# Nervo_Board_InMoov.net
KiCad netlist of a schematic drawn in EasyEDA
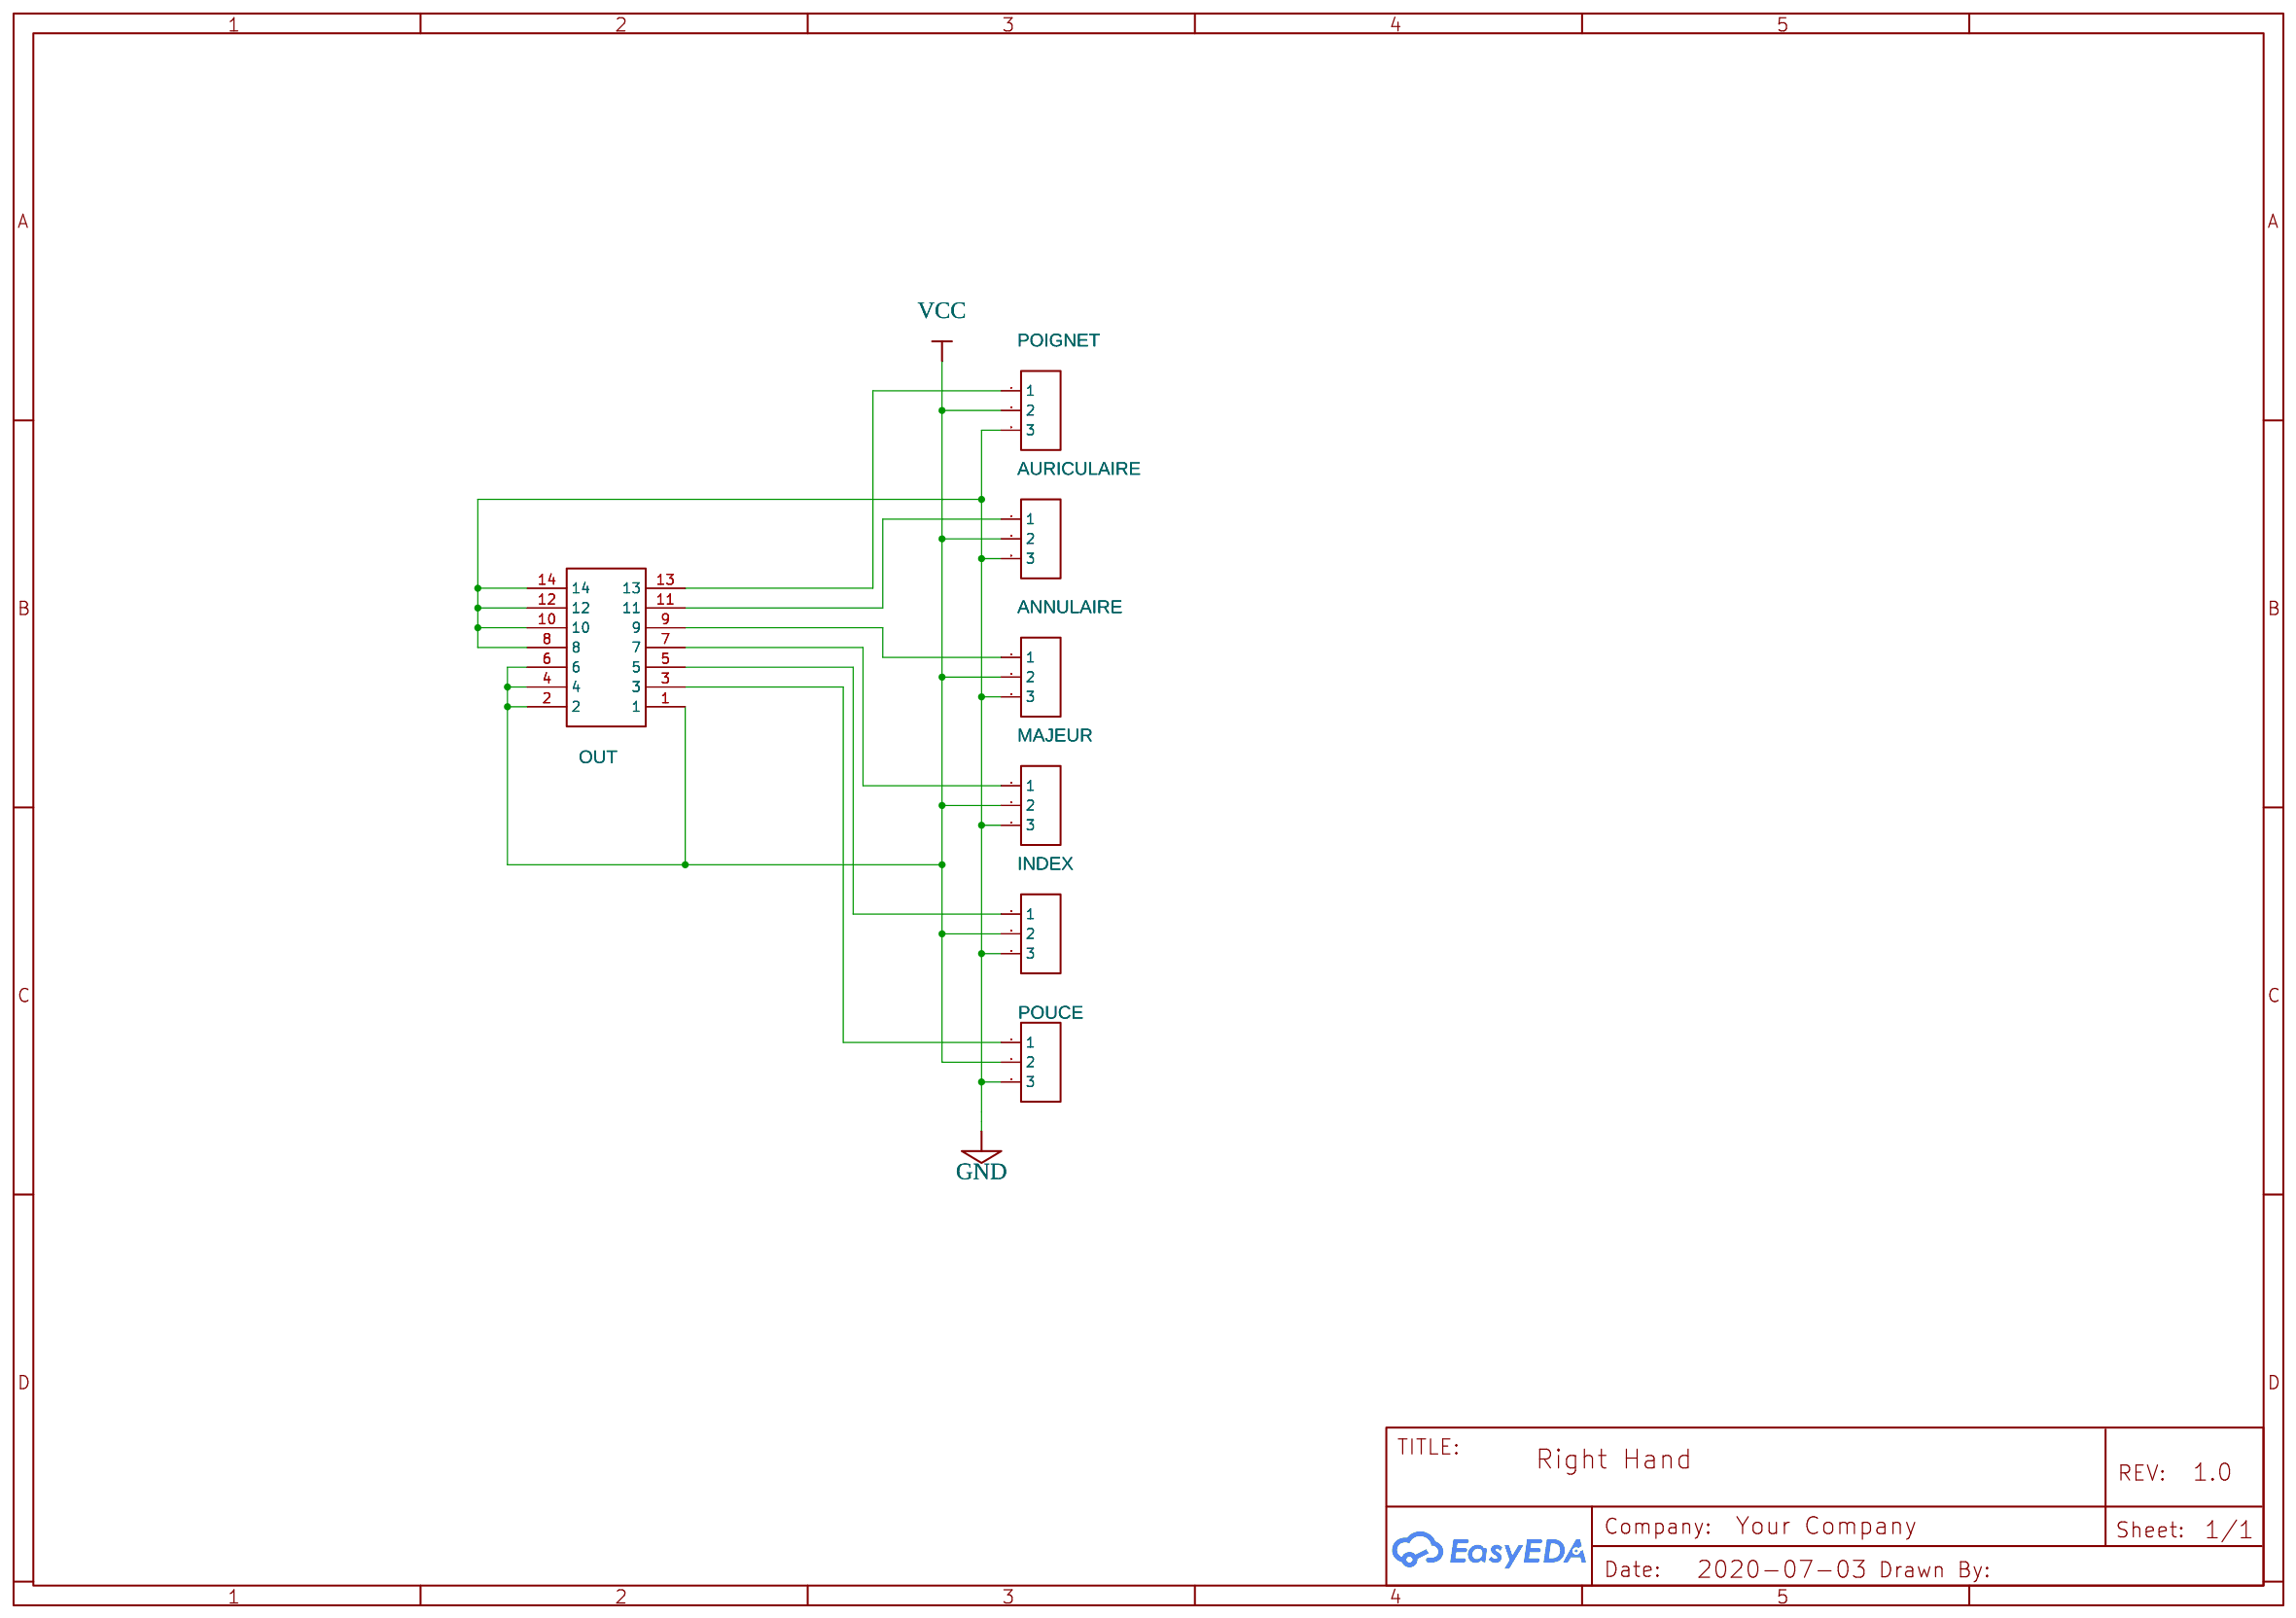
[diagram p0: schematic sheet]

(export (version "E")
  (design (tool "Eeschema 10.0.6"))
  (components
    (comp (ref "ANNULAIRE")
      (value "1")
      (fields
        (field (name "BOM_Manufacturer Part") "Header2.54mm 1*3P")
        (field (name "BOM_Supplier Part") "C49257")
      )
      (libsource (lib "") (part "Header-Male-2.54_1x3"))
    )
    (comp (ref "AURICULAIRE")
      (value "1")
      (fields
        (field (name "BOM_Manufacturer Part") "Header2.54mm 1*3P")
        (field (name "BOM_Supplier Part") "C49257")
      )
      (libsource (lib "") (part "Header-Male-2.54_1x3_2"))
    )
    (comp (ref "INDEX")
      (value "1")
      (fields
        (field (name "BOM_Manufacturer Part") "Header2.54mm 1*3P")
        (field (name "BOM_Supplier Part") "C49257")
      )
      (libsource (lib "") (part "Header-Male-2.54_1x3_3"))
    )
    (comp (ref "MAJEUR")
      (value "1")
      (fields
        (field (name "BOM_Manufacturer Part") "Header2.54mm 1*3P")
        (field (name "BOM_Supplier Part") "C49257")
      )
      (libsource (lib "") (part "Header-Male-2.54_1x3_5"))
    )
    (comp (ref "OUT")
      (value "Horn connector/2.0mm2*7P")
      (fields
        (field (name "BOM_Manufacturer Part") "Horn connector/2.0mm2*7P直简牛")
        (field (name "BOM_Supplier Part") "C29428")
      )
      (libsource (lib "") (part "Horn connector/2.0mm2*7P"))
    )
    (comp (ref "POIGNET")
      (value "1")
      (fields
        (field (name "BOM_Manufacturer Part") "Header2.54mm 1*3P")
        (field (name "BOM_Supplier Part") "C49257")
      )
      (libsource (lib "") (part "Header-Male-2.54_1x3_4"))
    )
    (comp (ref "POUCE")
      (value "1")
      (fields
        (field (name "BOM_Manufacturer Part") "Header2.54mm 1*3P")
        (field (name "BOM_Supplier Part") "C49257")
      )
      (libsource (lib "") (part "Header-Male-2.54_1x3_1"))
    )
  )
  (nets
    (net (code "1") (name "GND") (class "Default")
      (node (ref "ANNULAIRE") (pin "3") (pinfunction "3_3") (pintype "input"))
      (node (ref "AURICULAIRE") (pin "3") (pinfunction "3_3") (pintype "input"))
      (node (ref "INDEX") (pin "3") (pinfunction "3_3") (pintype "input"))
      (node (ref "MAJEUR") (pin "3") (pinfunction "3_3") (pintype "input"))
      (node (ref "OUT") (pin "10") (pinfunction "10_10") (pintype "unspecified"))
      (node (ref "OUT") (pin "12") (pinfunction "12_12") (pintype "unspecified"))
      (node (ref "OUT") (pin "14") (pinfunction "14_14") (pintype "unspecified"))
      (node (ref "OUT") (pin "8") (pinfunction "8_8") (pintype "unspecified"))
      (node (ref "POIGNET") (pin "3") (pinfunction "3_3") (pintype "input"))
      (node (ref "POUCE") (pin "3") (pinfunction "3_3") (pintype "input"))
    )
    (net (code "2") (name "Net-(ANNULAIRE-Pad1)") (class "Default")
      (node (ref "ANNULAIRE") (pin "1") (pinfunction "1_1") (pintype "input"))
      (node (ref "OUT") (pin "9") (pinfunction "9_9") (pintype "unspecified"))
    )
    (net (code "3") (name "Net-(AURICULAIRE-Pad1)") (class "Default")
      (node (ref "AURICULAIRE") (pin "1") (pinfunction "1_1") (pintype "input"))
      (node (ref "OUT") (pin "11") (pinfunction "11_11") (pintype "unspecified"))
    )
    (net (code "4") (name "Net-(INDEX-Pad1)") (class "Default")
      (node (ref "INDEX") (pin "1") (pinfunction "1_1") (pintype "input"))
      (node (ref "OUT") (pin "5") (pinfunction "5_5") (pintype "unspecified"))
    )
    (net (code "5") (name "Net-(MAJEUR-Pad1)") (class "Default")
      (node (ref "MAJEUR") (pin "1") (pinfunction "1_1") (pintype "input"))
      (node (ref "OUT") (pin "7") (pinfunction "7_7") (pintype "unspecified"))
    )
    (net (code "6") (name "Net-(OUT-Pad3)") (class "Default")
      (node (ref "OUT") (pin "3") (pinfunction "3_3") (pintype "unspecified"))
      (node (ref "POUCE") (pin "1") (pinfunction "1_1") (pintype "input"))
    )
    (net (code "7") (name "Net-(OUT-Pad13)") (class "Default")
      (node (ref "OUT") (pin "13") (pinfunction "13_13") (pintype "unspecified"))
      (node (ref "POIGNET") (pin "1") (pinfunction "1_1") (pintype "input"))
    )
    (net (code "8") (name "VCC") (class "Default")
      (node (ref "ANNULAIRE") (pin "2") (pinfunction "2_2") (pintype "input"))
      (node (ref "AURICULAIRE") (pin "2") (pinfunction "2_2") (pintype "input"))
      (node (ref "INDEX") (pin "2") (pinfunction "2_2") (pintype "input"))
      (node (ref "MAJEUR") (pin "2") (pinfunction "2_2") (pintype "input"))
      (node (ref "OUT") (pin "1") (pinfunction "1_1") (pintype "unspecified"))
      (node (ref "OUT") (pin "2") (pinfunction "2_2") (pintype "unspecified"))
      (node (ref "OUT") (pin "4") (pinfunction "4_4") (pintype "unspecified"))
      (node (ref "OUT") (pin "6") (pinfunction "6_6") (pintype "unspecified"))
      (node (ref "POIGNET") (pin "2") (pinfunction "2_2") (pintype "input"))
      (node (ref "POUCE") (pin "2") (pinfunction "2_2") (pintype "input"))
    )
  )
)
